# 2024.net
KiCad netlist of a schematic drawn in EasyEDA Pro
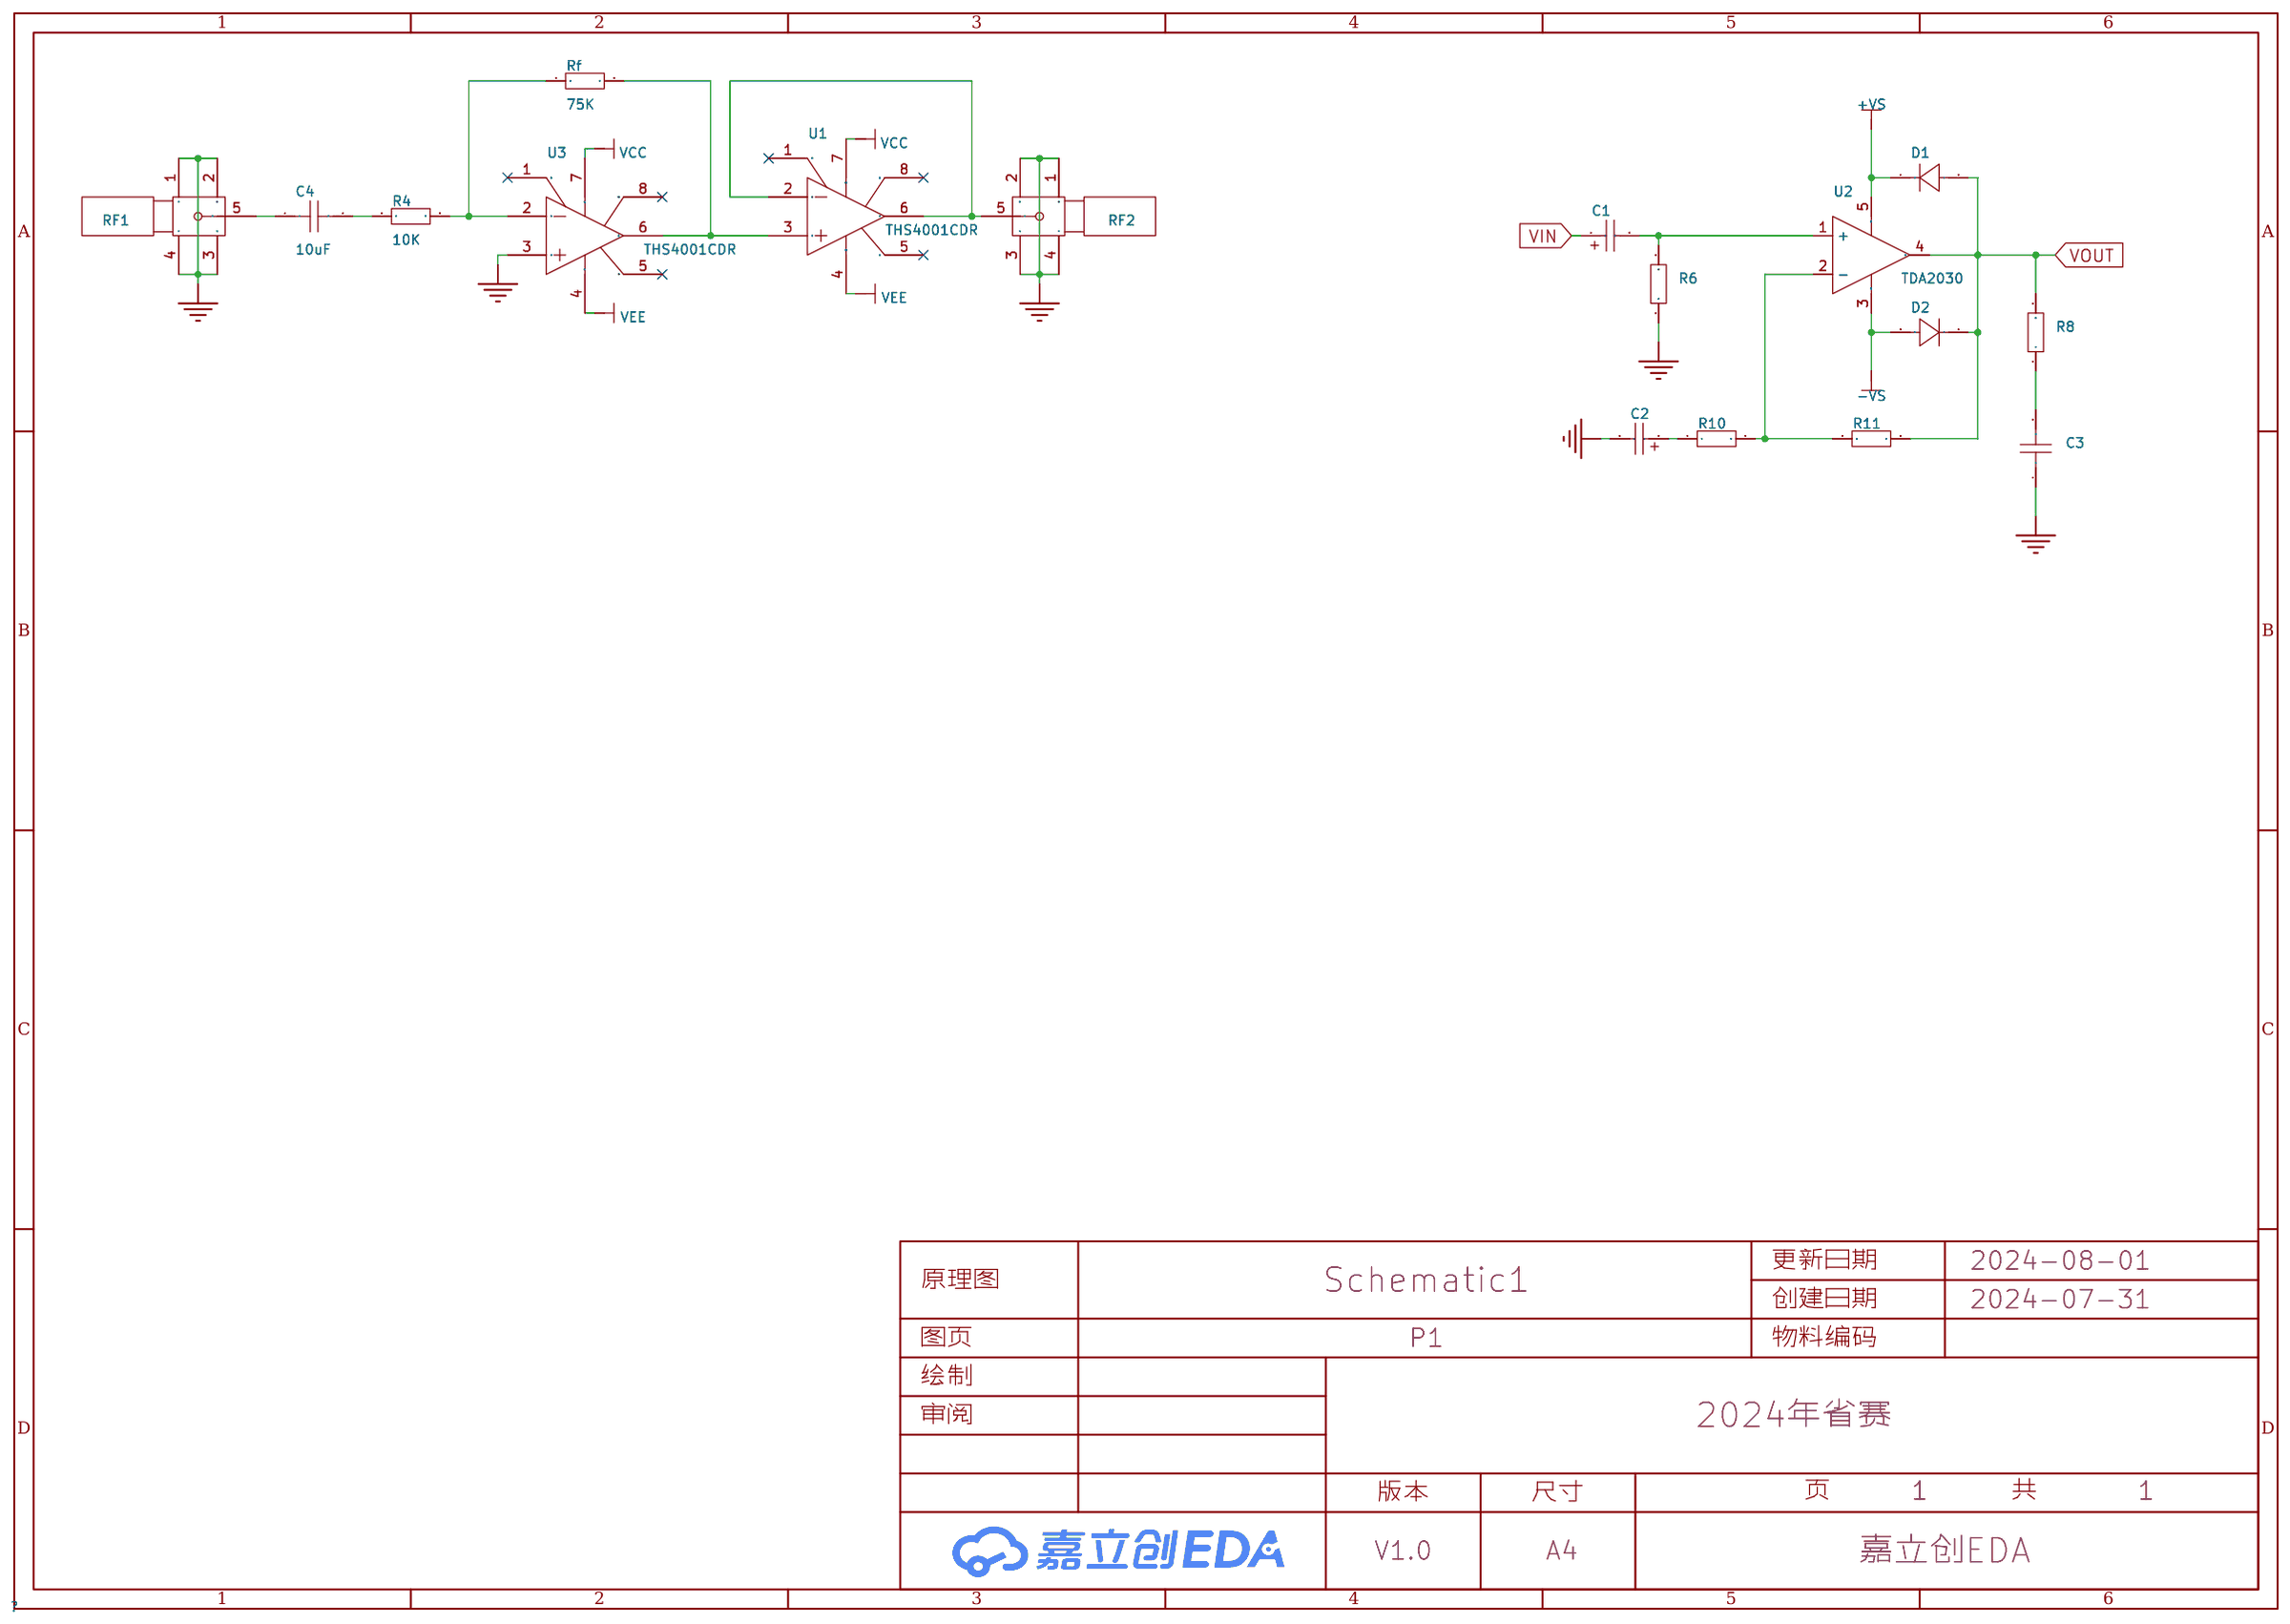
[diagram p0: schematic sheet]

(export (version "E")
  (design (tool "Eeschema 10.0.6"))
  (components
    (comp (ref "C1")
      (value "1uF")
      (footprint "easyedapro:CAP-SMD_L3.2-W1.6-RD-C7171")
      (description "容值:10uF;精度:±10%;额定电压:16V;等效串联电阻:3Ω@100kHz;")
      (fields (field (name "Manufacturer Part") "TAJA106K016RNJ") (field (name "Manufacturer") "Kyocera AVX"))
      (libsource (lib "easyedapro") (part "TAJA106K016RNJ"))
    )
    (comp (ref "C2")
      (value "22uF")
      (footprint "easyedapro:C_Ele_SMD_3x5.4mm")
      (libsource (lib "easyedapro") (part "CAP"))
    )
    (comp (ref "C3")
      (value "220n")
      (footprint "easyedapro:C0603")
      (libsource (lib "easyedapro") (part "CapAcitance"))
    )
    (comp (ref "C4")
      (value "10uF")
      (footprint "easyedapro:C0603")
      (libsource (lib "easyedapro") (part "CapAcitance"))
    )
    (comp (ref "D1")
      (value "~")
      (footprint "easyedapro:DO_1N4007")
      (libsource (lib "easyedapro") (part "D_1N4007"))
    )
    (comp (ref "D2")
      (value "~")
      (footprint "easyedapro:DO_1N4007")
      (libsource (lib "easyedapro") (part "D_1N4007"))
    )
    (comp (ref "R4") (value "10K") (footprint "easyedapro:R0603") (libsource (lib "easyedapro") (part "电阻")))
    (comp (ref "R6") (value "22K") (footprint "easyedapro:R0603") (libsource (lib "easyedapro") (part "电阻")))
    (comp (ref "R8") (value "1") (footprint "easyedapro:R0603") (libsource (lib "easyedapro") (part "电阻")))
    (comp (ref "R10") (value "680") (footprint "easyedapro:R0603") (libsource (lib "easyedapro") (part "电阻")))
    (comp (ref "R11") (value "10K") (footprint "easyedapro:R0603") (libsource (lib "easyedapro") (part "电阻")))
    (comp (ref "Rf") (value "75K") (footprint "easyedapro:R0603") (libsource (lib "easyedapro") (part "电阻")))
    (comp (ref "RF1")
      (value "BWSMA-KE-P001")
      (footprint "easyedapro:SMA-SMD_BWSMA-KE-P001")
      (description "连接器类型:板端;接口类型:内孔;端口数量:1;接口直径:5.2mm;接口长度/高度:-;频率-最大值:-;射频系列:SMA;阻抗:50Ω;样式:偏脚;工作温度范围:-;")
      (fields (field (name "Manufacturer") "BAT WIRELESS(蝙蝠无线)"))
      (libsource (lib "easyedapro") (part "BWSMA-KE-P001"))
    )
    (comp (ref "RF2")
      (value "BWSMA-KE-P001")
      (footprint "easyedapro:SMA-SMD_BWSMA-KE-P001")
      (description "连接器类型:板端;接口类型:内孔;端口数量:1;接口直径:5.2mm;接口长度/高度:-;频率-最大值:-;射频系列:SMA;阻抗:50Ω;样式:偏脚;工作温度范围:-;")
      (fields (field (name "Manufacturer") "BAT WIRELESS(蝙蝠无线)"))
      (libsource (lib "easyedapro") (part "BWSMA-KE-P001"))
    )
    (comp (ref "U1")
      (value "THS4001CDR")
      (footprint "easyedapro:SOIC-8_L4.9-W3.9-P1.27-LS6.0-BL")
      (description "放大器数:单路;增益带宽积(GBP):270MHz;输入偏置电流(Ib):2.6uA;压摆率(SR):400V/us;带宽(-3db):270MHz;")
      (fields (field (name "Manufacturer") "TI(德州仪器)"))
      (libsource (lib "easyedapro") (part "THS4001CDR"))
    )
    (comp (ref "U2")
      (value "TDA2030")
      (footprint "easyedapro:TO-220-5_L10.2-W4.8-P1.70-TL")
      (description "TDA2030AL-TB5-T TDA2030 TDA2030L-TB5-T TFA2050")
      (fields (field (name "Manufacturer") "JSMSEMI(杰盛微)"))
      (libsource (lib "easyedapro") (part "TDA2030_C5296731"))
    )
    (comp (ref "U3")
      (value "THS4001CDR")
      (footprint "easyedapro:SOIC-8_L4.9-W3.9-P1.27-LS6.0-BL")
      (description "放大器数:单路;增益带宽积(GBP):270MHz;输入偏置电流(Ib):2.6uA;压摆率(SR):400V/us;带宽(-3db):270MHz;")
      (fields (field (name "Manufacturer") "TI(德州仪器)"))
      (libsource (lib "easyedapro") (part "THS4001CDR"))
    )
  )
  (nets
    (net (code "1") (name "+VS") (class "Default")
      (node (ref "D1") (pin "1") (pinfunction "K_1") (pintype "input"))
      (node (ref "U2") (pin "5") (pinfunction "VCC+_5") (pintype "unspecified"))
    )
    (net (code "2") (name "-VS") (class "Default")
      (node (ref "D2") (pin "2") (pinfunction "A_2") (pintype "input"))
      (node (ref "U2") (pin "3") (pinfunction "GND_3") (pintype "unspecified"))
    )
    (net (code "3") (name "GND") (class "Default")
      (node (ref "C2") (pin "2") (pinfunction "2_2") (pintype "input"))
      (node (ref "C3") (pin "1") (pinfunction "1_1") (pintype "input"))
      (node (ref "R6") (pin "1") (pinfunction "1_1") (pintype "input"))
      (node (ref "RF1") (pin "1") (pinfunction "1_1") (pintype "unspecified"))
      (node (ref "RF1") (pin "2") (pinfunction "2_2") (pintype "unspecified"))
      (node (ref "RF1") (pin "3") (pinfunction "3_3") (pintype "unspecified"))
      (node (ref "RF1") (pin "4") (pinfunction "4_4") (pintype "unspecified"))
      (node (ref "RF2") (pin "1") (pinfunction "1_1") (pintype "unspecified"))
      (node (ref "RF2") (pin "2") (pinfunction "2_2") (pintype "unspecified"))
      (node (ref "RF2") (pin "3") (pinfunction "3_3") (pintype "unspecified"))
      (node (ref "RF2") (pin "4") (pinfunction "4_4") (pintype "unspecified"))
      (node (ref "U3") (pin "3") (pinfunction "IN+_3") (pintype "unspecified"))
    )
    (net (code "4") (name "Net-(C2-Pad1)") (class "Default")
      (node (ref "C2") (pin "1") (pinfunction "1_1") (pintype "input"))
      (node (ref "R10") (pin "1") (pinfunction "1_1") (pintype "input"))
    )
    (net (code "5") (name "Net-(C3-Pad2)") (class "Default")
      (node (ref "C3") (pin "2") (pinfunction "2_2") (pintype "input"))
      (node (ref "R8") (pin "1") (pinfunction "1_1") (pintype "input"))
    )
    (net (code "6") (name "Net-(C4-Pad1)") (class "Default")
      (node (ref "C4") (pin "1") (pinfunction "1_1") (pintype "input"))
      (node (ref "RF1") (pin "5") (pinfunction "5_5") (pintype "unspecified"))
    )
    (net (code "7") (name "Net-(C4-Pad2)") (class "Default")
      (node (ref "C4") (pin "2") (pinfunction "2_2") (pintype "input"))
      (node (ref "R4") (pin "1") (pinfunction "1_1") (pintype "input"))
    )
    (net (code "8") (name "Net-(U1-IN+)") (class "Default")
      (node (ref "Rf") (pin "2") (pinfunction "2_2") (pintype "input"))
      (node (ref "U1") (pin "3") (pinfunction "IN+_3") (pintype "unspecified"))
      (node (ref "U3") (pin "6") (pinfunction "OUT_6") (pintype "output"))
    )
    (net (code "9") (name "Net-(U1-IN-)") (class "Default")
      (node (ref "RF2") (pin "5") (pinfunction "5_5") (pintype "unspecified"))
      (node (ref "U1") (pin "2") (pinfunction "IN-_2") (pintype "unspecified"))
      (node (ref "U1") (pin "6") (pinfunction "OUT_6") (pintype "output"))
    )
    (net (code "10") (name "Net-(U2-+)") (class "Default")
      (node (ref "C1") (pin "2") (pinfunction "2_2") (pintype "input"))
      (node (ref "R6") (pin "2") (pinfunction "2_2") (pintype "input"))
      (node (ref "U2") (pin "1") (pinfunction "+_1") (pintype "unspecified"))
    )
    (net (code "11") (name "Net-(U2--)") (class "Default")
      (node (ref "R10") (pin "2") (pinfunction "2_2") (pintype "input"))
      (node (ref "R11") (pin "1") (pinfunction "1_1") (pintype "input"))
      (node (ref "U2") (pin "2") (pinfunction "-_2") (pintype "unspecified"))
    )
    (net (code "12") (name "Net-(U3-IN-)") (class "Default")
      (node (ref "R4") (pin "2") (pinfunction "2_2") (pintype "input"))
      (node (ref "Rf") (pin "1") (pinfunction "1_1") (pintype "input"))
      (node (ref "U3") (pin "2") (pinfunction "IN-_2") (pintype "unspecified"))
    )
    (net (code "13") (name "VCC") (class "Default")
      (node (ref "U1") (pin "7") (pinfunction "VCC+_7") (pintype "unspecified"))
      (node (ref "U3") (pin "7") (pinfunction "VCC+_7") (pintype "unspecified"))
    )
    (net (code "14") (name "VEE") (class "Default")
      (node (ref "U1") (pin "4") (pinfunction "VCC-_4") (pintype "unspecified"))
      (node (ref "U3") (pin "4") (pinfunction "VCC-_4") (pintype "unspecified"))
    )
    (net (code "15") (name "VIN") (class "Default")
      (node (ref "C1") (pin "1") (pinfunction "1_1") (pintype "input"))
    )
    (net (code "16") (name "VOUT") (class "Default")
      (node (ref "D1") (pin "2") (pinfunction "A_2") (pintype "input"))
      (node (ref "D2") (pin "1") (pinfunction "K_1") (pintype "input"))
      (node (ref "R11") (pin "2") (pinfunction "2_2") (pintype "input"))
      (node (ref "R8") (pin "2") (pinfunction "2_2") (pintype "input"))
      (node (ref "U2") (pin "4") (pinfunction "OUT_4") (pintype "unspecified"))
    )
    (net (code "17") (name "unconnected-(U1-NC-Pad5)") (class "Default")
      (node (ref "U1") (pin "5") (pinfunction "NC_5") (pintype "unspecified+no_connect"))
    )
    (net (code "18") (name "unconnected-(U1-NULL-Pad1)") (class "Default")
      (node (ref "U1") (pin "1") (pinfunction "NULL_1") (pintype "unspecified+no_connect"))
    )
    (net (code "19") (name "unconnected-(U1-NULL-Pad8)") (class "Default")
      (node (ref "U1") (pin "8") (pinfunction "NULL_8") (pintype "unspecified+no_connect"))
    )
    (net (code "20") (name "unconnected-(U3-NC-Pad5)") (class "Default")
      (node (ref "U3") (pin "5") (pinfunction "NC_5") (pintype "unspecified+no_connect"))
    )
    (net (code "21") (name "unconnected-(U3-NULL-Pad1)") (class "Default")
      (node (ref "U3") (pin "1") (pinfunction "NULL_1") (pintype "unspecified+no_connect"))
    )
    (net (code "22") (name "unconnected-(U3-NULL-Pad8)") (class "Default")
      (node (ref "U3") (pin "8") (pinfunction "NULL_8") (pintype "unspecified+no_connect"))
    )
  )
)
